# manual_power.net
KiCad netlist of a schematic drawn in EAGLE
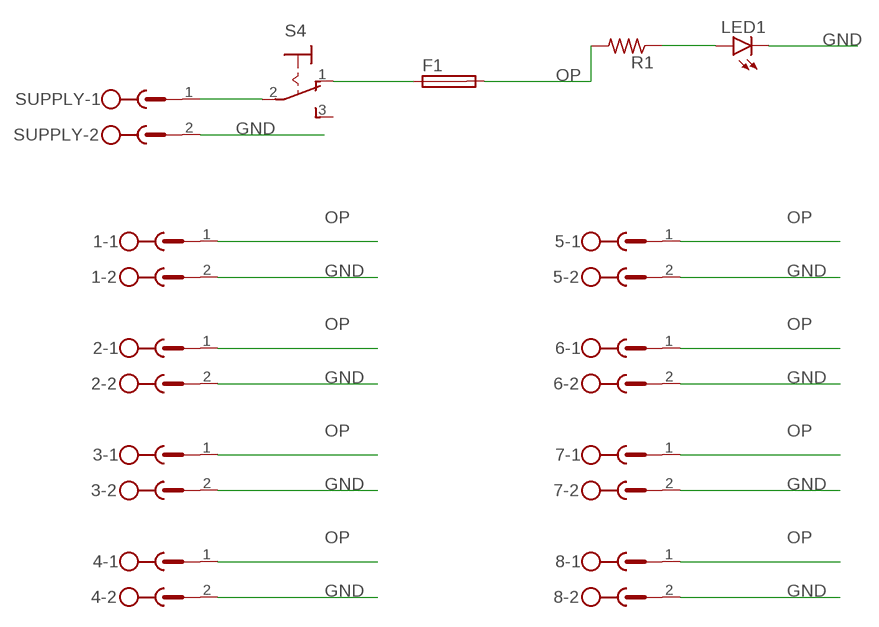
[diagram p0: schematic, sheet 1]

(export (version "E")
  (design (tool "Eeschema 10.0.6"))
  (components
    (comp (ref "1")
      (value "MSTBV2")
      (footprint "eagle-import:MSTBV2")
      (libsource (lib "eagle-import") (part "MSTBV2"))
    )
    (comp (ref "2")
      (value "MSTBV2")
      (footprint "eagle-import:MSTBV2")
      (libsource (lib "eagle-import") (part "MSTBV2"))
    )
    (comp (ref "3")
      (value "MSTBV2")
      (footprint "eagle-import:MSTBV2")
      (libsource (lib "eagle-import") (part "MSTBV2"))
    )
    (comp (ref "4")
      (value "MSTBV2")
      (footprint "eagle-import:MSTBV2")
      (libsource (lib "eagle-import") (part "MSTBV2"))
    )
    (comp (ref "5")
      (value "MSTBV2")
      (footprint "eagle-import:MSTBV2")
      (libsource (lib "eagle-import") (part "MSTBV2"))
    )
    (comp (ref "6")
      (value "MSTBV2")
      (footprint "eagle-import:MSTBV2")
      (libsource (lib "eagle-import") (part "MSTBV2"))
    )
    (comp (ref "7")
      (value "MSTBV2")
      (footprint "eagle-import:MSTBV2")
      (libsource (lib "eagle-import") (part "MSTBV2"))
    )
    (comp (ref "8")
      (value "MSTBV2")
      (footprint "eagle-import:MSTBV2")
      (libsource (lib "eagle-import") (part "MSTBV2"))
    )
    (comp (ref "F1")
      (value "SH22")
      (footprint "eagle-import:SH22")
      (libsource (lib "eagle-import") (part "SH22"))
    )
    (comp (ref "LED1")
      (value "LED5MM")
      (footprint "eagle-import:LED5MM")
      (libsource (lib "eagle-import") (part "LED5MM"))
    )
    (comp (ref "R1")
      (value "R-US_0207/10")
      (footprint "eagle-import:0207_10")
      (libsource (lib "eagle-import") (part "R-US_0207/10"))
    )
    (comp (ref "S4")
      (value "320-916")
      (footprint "eagle-import:320-916")
      (libsource (lib "eagle-import") (part "320-916"))
    )
    (comp (ref "SUPPLY")
      (value "MSTBV2")
      (footprint "eagle-import:MSTBV2")
      (libsource (lib "eagle-import") (part "MSTBV2"))
    )
  )
  (nets
    (net (code "1") (name "/GND") (class "Default")
      (node (ref "1") (pin "2") (pinfunction "SK_2") (pintype "passive"))
      (node (ref "2") (pin "2") (pinfunction "SK_2") (pintype "passive"))
      (node (ref "3") (pin "2") (pinfunction "SK_2") (pintype "passive"))
      (node (ref "4") (pin "2") (pinfunction "SK_2") (pintype "passive"))
      (node (ref "5") (pin "2") (pinfunction "SK_2") (pintype "passive"))
      (node (ref "6") (pin "2") (pinfunction "SK_2") (pintype "passive"))
      (node (ref "7") (pin "2") (pinfunction "SK_2") (pintype "passive"))
      (node (ref "8") (pin "2") (pinfunction "SK_2") (pintype "passive"))
      (node (ref "LED1") (pin "K") (pinfunction "C_K") (pintype "passive"))
      (node (ref "SUPPLY") (pin "2") (pinfunction "SK_2") (pintype "passive"))
    )
    (net (code "2") (name "/OP") (class "Default")
      (node (ref "1") (pin "1") (pinfunction "SK_1") (pintype "passive"))
      (node (ref "2") (pin "1") (pinfunction "SK_1") (pintype "passive"))
      (node (ref "3") (pin "1") (pinfunction "SK_1") (pintype "passive"))
      (node (ref "4") (pin "1") (pinfunction "SK_1") (pintype "passive"))
      (node (ref "5") (pin "1") (pinfunction "SK_1") (pintype "passive"))
      (node (ref "6") (pin "1") (pinfunction "SK_1") (pintype "passive"))
      (node (ref "7") (pin "1") (pinfunction "SK_1") (pintype "passive"))
      (node (ref "8") (pin "1") (pinfunction "SK_1") (pintype "passive"))
      (node (ref "F1") (pin "2") (pinfunction "2_2") (pintype "passive"))
      (node (ref "R1") (pin "2") (pinfunction "2_2") (pintype "passive"))
    )
    (net (code "3") (name "Net-(LED1-PadA)") (class "Default")
      (node (ref "LED1") (pin "A") (pinfunction "A_A") (pintype "passive"))
      (node (ref "R1") (pin "1") (pinfunction "1_1") (pintype "passive"))
    )
    (net (code "4") (name "Net-(S4-O)") (class "Default")
      (node (ref "F1") (pin "1") (pinfunction "1_1") (pintype "passive"))
      (node (ref "S4") (pin "1") (pinfunction "O_1") (pintype "passive"))
    )
    (net (code "5") (name "Net-(S4-P)") (class "Default")
      (node (ref "S4") (pin "2") (pinfunction "P_2") (pintype "passive"))
      (node (ref "SUPPLY") (pin "1") (pinfunction "SK_1") (pintype "passive"))
    )
    (net (code "6") (name "unconnected-(S4-S-Pad3)") (class "Default")
      (node (ref "S4") (pin "3") (pinfunction "S_3") (pintype "passive"))
    )
  )
)
